# BLDC_Motor_Controller_2018_Rev1.net
KiCad netlist of a schematic drawn in EAGLE
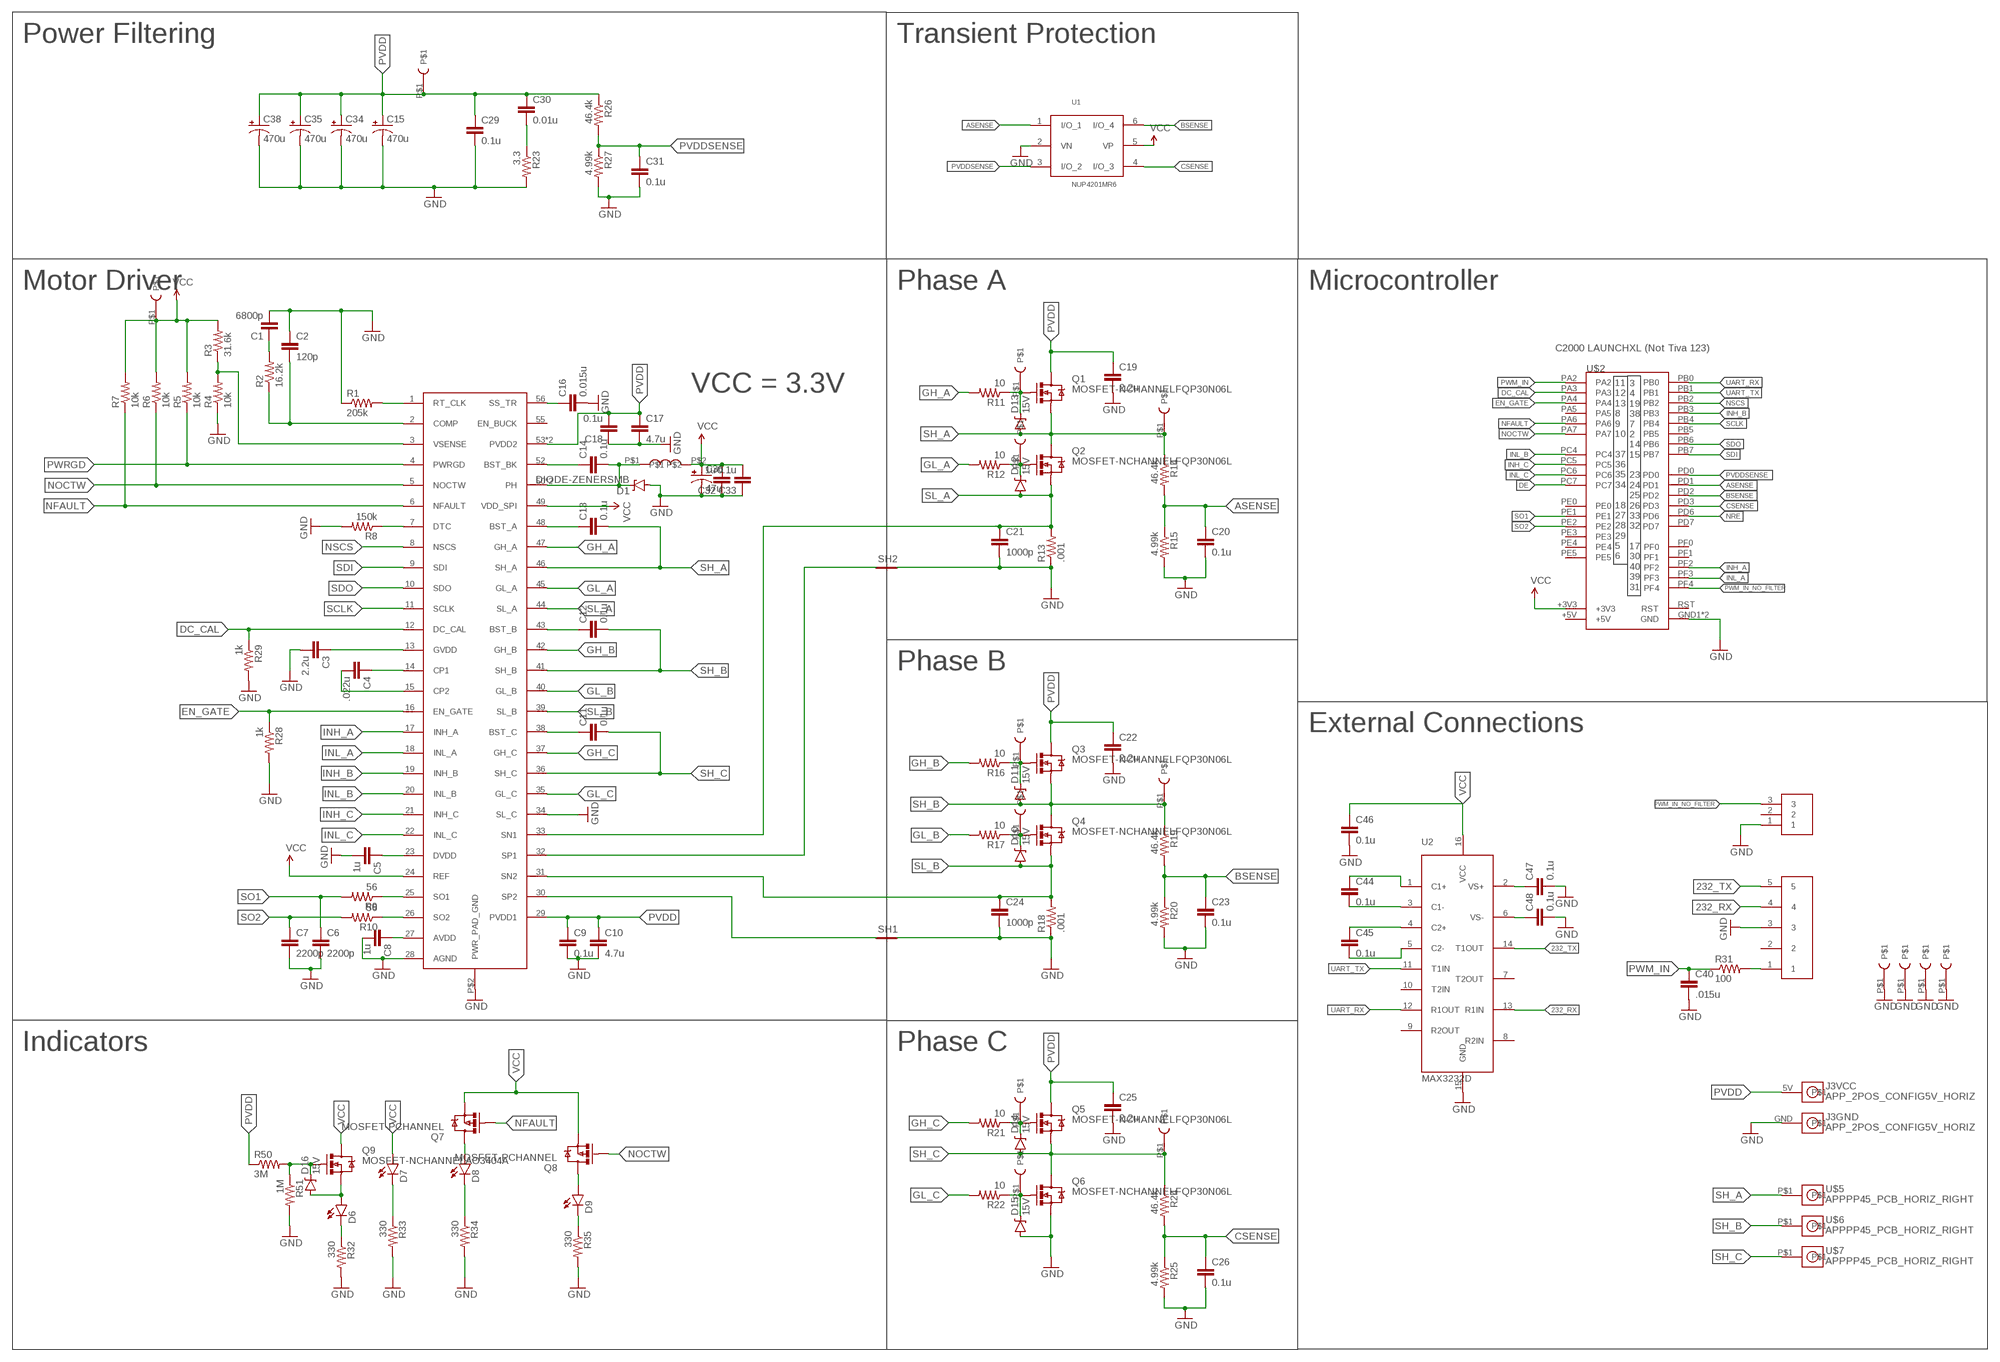
[diagram p0: schematic, sheet 1]

(export (version "E")
  (design (tool "Eeschema 10.0.6"))
  (components
    (comp (ref "C1")
      (value "6800p")
      (footprint "eagle-import:0805")
      (libsource (lib "eagle-import") (part "CAP0805"))
    )
    (comp (ref "C2")
      (value "120p")
      (footprint "eagle-import:0805")
      (libsource (lib "eagle-import") (part "CAP0805"))
    )
    (comp (ref "C3")
      (value "2.2u")
      (footprint "eagle-import:1206")
      (libsource (lib "eagle-import") (part "CAP1206"))
    )
    (comp (ref "C4")
      (value ".022u")
      (footprint "eagle-import:0805")
      (libsource (lib "eagle-import") (part "CAP0805"))
    )
    (comp (ref "C5")
      (value "1u")
      (footprint "eagle-import:0805")
      (libsource (lib "eagle-import") (part "CAP0805"))
    )
    (comp (ref "C6")
      (value "2200p")
      (footprint "eagle-import:0805")
      (libsource (lib "eagle-import") (part "CAP0805"))
    )
    (comp (ref "C7")
      (value "2200p")
      (footprint "eagle-import:0805")
      (libsource (lib "eagle-import") (part "CAP0805"))
    )
    (comp (ref "C8")
      (value "1u")
      (footprint "eagle-import:0805")
      (libsource (lib "eagle-import") (part "CAP0805"))
    )
    (comp (ref "C9")
      (value "0.1u")
      (footprint "eagle-import:0805")
      (libsource (lib "eagle-import") (part "CAP0805"))
    )
    (comp (ref "C10")
      (value "4.7u")
      (footprint "eagle-import:1206")
      (libsource (lib "eagle-import") (part "CAP1206"))
    )
    (comp (ref "C11")
      (value "0.1u")
      (footprint "eagle-import:0805")
      (libsource (lib "eagle-import") (part "CAP0805"))
    )
    (comp (ref "C12")
      (value "0.1u")
      (footprint "eagle-import:0805")
      (libsource (lib "eagle-import") (part "CAP0805"))
    )
    (comp (ref "C13")
      (value "0.1u")
      (footprint "eagle-import:0805")
      (libsource (lib "eagle-import") (part "CAP0805"))
    )
    (comp (ref "C14")
      (value "0.1u")
      (footprint "eagle-import:0805")
      (libsource (lib "eagle-import") (part "CAP0805"))
    )
    (comp (ref "C15")
      (value "470u")
      (footprint "eagle-import:CPOL-RADIAL-1000UF-25V")
      (libsource (lib "eagle-import") (part "CAP_POLPTH4"))
    )
    (comp (ref "C16")
      (value "0.015u")
      (footprint "eagle-import:0805")
      (libsource (lib "eagle-import") (part "CAP0805"))
    )
    (comp (ref "C17")
      (value "4.7u")
      (footprint "eagle-import:1206")
      (libsource (lib "eagle-import") (part "CAP1206"))
    )
    (comp (ref "C18")
      (value "0.1u")
      (footprint "eagle-import:0805")
      (libsource (lib "eagle-import") (part "CAP0805"))
    )
    (comp (ref "C19")
      (value "2.2u")
      (footprint "eagle-import:1206")
      (libsource (lib "eagle-import") (part "CAP1206"))
    )
    (comp (ref "C20")
      (value "0.1u")
      (footprint "eagle-import:0805")
      (libsource (lib "eagle-import") (part "CAP0805"))
    )
    (comp (ref "C21")
      (value "1000p")
      (footprint "eagle-import:0805")
      (libsource (lib "eagle-import") (part "CAP0805"))
    )
    (comp (ref "C22")
      (value "2.2u")
      (footprint "eagle-import:1206")
      (libsource (lib "eagle-import") (part "CAP1206"))
    )
    (comp (ref "C23")
      (value "0.1u")
      (footprint "eagle-import:0805")
      (libsource (lib "eagle-import") (part "CAP0805"))
    )
    (comp (ref "C24")
      (value "1000p")
      (footprint "eagle-import:0805")
      (libsource (lib "eagle-import") (part "CAP0805"))
    )
    (comp (ref "C25")
      (value "2.2u")
      (footprint "eagle-import:1206")
      (libsource (lib "eagle-import") (part "CAP1206"))
    )
    (comp (ref "C26")
      (value "0.1u")
      (footprint "eagle-import:0805")
      (libsource (lib "eagle-import") (part "CAP0805"))
    )
    (comp (ref "C29")
      (value "0.1u")
      (footprint "eagle-import:0805")
      (libsource (lib "eagle-import") (part "CAP0805"))
    )
    (comp (ref "C30")
      (value "0.01u")
      (footprint "eagle-import:0805")
      (libsource (lib "eagle-import") (part "CAP0805"))
    )
    (comp (ref "C31")
      (value "0.1u")
      (footprint "eagle-import:0805")
      (libsource (lib "eagle-import") (part "CAP0805"))
    )
    (comp (ref "C32")
      (value "1u")
      (footprint "eagle-import:0805")
      (libsource (lib "eagle-import") (part "CAP0805"))
    )
    (comp (ref "C33")
      (value "0.1u")
      (footprint "eagle-import:0805")
      (libsource (lib "eagle-import") (part "CAP0805"))
    )
    (comp (ref "C34")
      (value "470u")
      (footprint "eagle-import:CPOL-RADIAL-1000UF-25V")
      (libsource (lib "eagle-import") (part "CAP_POLPTH4"))
    )
    (comp (ref "C35")
      (value "470u")
      (footprint "eagle-import:CPOL-RADIAL-1000UF-25V")
      (libsource (lib "eagle-import") (part "CAP_POLPTH4"))
    )
    (comp (ref "C36")
      (value "47u")
      (footprint "eagle-import:CPOL-RADIAL-100UF-25V")
      (libsource (lib "eagle-import") (part "CAP_POLPTH1"))
    )
    (comp (ref "C38")
      (value "470u")
      (footprint "eagle-import:CPOL-RADIAL-1000UF-25V")
      (libsource (lib "eagle-import") (part "CAP_POLPTH4"))
    )
    (comp (ref "C40")
      (value ".015u")
      (footprint "eagle-import:0805")
      (libsource (lib "eagle-import") (part "CAP0805"))
    )
    (comp (ref "C44")
      (value "0.1u")
      (footprint "eagle-import:0805")
      (libsource (lib "eagle-import") (part "CAP0805"))
    )
    (comp (ref "C45")
      (value "0.1u")
      (footprint "eagle-import:0805")
      (libsource (lib "eagle-import") (part "CAP0805"))
    )
    (comp (ref "C46")
      (value "0.1u")
      (footprint "eagle-import:0805")
      (libsource (lib "eagle-import") (part "CAP0805"))
    )
    (comp (ref "C47")
      (value "0.1u")
      (footprint "eagle-import:0805")
      (libsource (lib "eagle-import") (part "CAP0805"))
    )
    (comp (ref "C48")
      (value "0.1u")
      (footprint "eagle-import:0805")
      (libsource (lib "eagle-import") (part "CAP0805"))
    )
    (comp (ref "D1")
      (value "DIODE-ZENERSMB")
      (footprint "eagle-import:SMB-DIODE")
      (libsource (lib "eagle-import") (part "DIODE-ZENERSMB"))
    )
    (comp (ref "D6")
      (value "LED1206")
      (footprint "eagle-import:LED-1206")
      (libsource (lib "eagle-import") (part "LED1206"))
    )
    (comp (ref "D7")
      (value "LED1206")
      (footprint "eagle-import:LED-1206")
      (libsource (lib "eagle-import") (part "LED1206"))
    )
    (comp (ref "D8")
      (value "LED1206")
      (footprint "eagle-import:LED-1206")
      (libsource (lib "eagle-import") (part "LED1206"))
    )
    (comp (ref "D9")
      (value "LED1206")
      (footprint "eagle-import:LED-1206")
      (libsource (lib "eagle-import") (part "LED1206"))
    )
    (comp (ref "D10")
      (value "15V")
      (footprint "eagle-import:SOD-323")
      (libsource (lib "eagle-import") (part "DIODE-ZENER3.3V"))
    )
    (comp (ref "D11")
      (value "15V")
      (footprint "eagle-import:SOD-323")
      (libsource (lib "eagle-import") (part "DIODE-ZENER3.3V"))
    )
    (comp (ref "D12")
      (value "15V")
      (footprint "eagle-import:SOD-323")
      (libsource (lib "eagle-import") (part "DIODE-ZENER3.3V"))
    )
    (comp (ref "D13")
      (value "15V")
      (footprint "eagle-import:SOD-323")
      (libsource (lib "eagle-import") (part "DIODE-ZENER3.3V"))
    )
    (comp (ref "D14")
      (value "15V")
      (footprint "eagle-import:SOD-323")
      (libsource (lib "eagle-import") (part "DIODE-ZENER3.3V"))
    )
    (comp (ref "D15")
      (value "15V")
      (footprint "eagle-import:SOD-323")
      (libsource (lib "eagle-import") (part "DIODE-ZENER3.3V"))
    )
    (comp (ref "D16")
      (value "15V")
      (footprint "eagle-import:SOD-323")
      (libsource (lib "eagle-import") (part "DIODE-ZENER3.3V"))
    )
    (comp (ref "J1")
      (value "SL03THROUGH_HOLE")
      (footprint "eagle-import:MOLEX_SL_03_TH")
      (fields (field (name "PARTNO") "0705550002"))
      (libsource (lib "eagle-import") (part "SL03THROUGH_HOLE"))
    )
    (comp (ref "J3")
      (value "APP_2POS_CONFIG5V_HORIZ")
      (footprint "eagle-import:APP45_5V_HORIZ_CONFIG")
      (libsource (lib "eagle-import") (part "APP_2POS_CONFIG5V_HORIZ"))
    )
    (comp (ref "Q1")
      (value "MOSFET-NCHANNELFQP30N06L")
      (footprint "eagle-import:TO220V")
      (libsource (lib "eagle-import") (part "MOSFET-NCHANNELFQP30N06L"))
    )
    (comp (ref "Q2")
      (value "MOSFET-NCHANNELFQP30N06L")
      (footprint "eagle-import:TO220V")
      (libsource (lib "eagle-import") (part "MOSFET-NCHANNELFQP30N06L"))
    )
    (comp (ref "Q3")
      (value "MOSFET-NCHANNELFQP30N06L")
      (footprint "eagle-import:TO220V")
      (libsource (lib "eagle-import") (part "MOSFET-NCHANNELFQP30N06L"))
    )
    (comp (ref "Q4")
      (value "MOSFET-NCHANNELFQP30N06L")
      (footprint "eagle-import:TO220V")
      (libsource (lib "eagle-import") (part "MOSFET-NCHANNELFQP30N06L"))
    )
    (comp (ref "Q5")
      (value "MOSFET-NCHANNELFQP30N06L")
      (footprint "eagle-import:TO220V")
      (libsource (lib "eagle-import") (part "MOSFET-NCHANNELFQP30N06L"))
    )
    (comp (ref "Q6")
      (value "MOSFET-NCHANNELFQP30N06L")
      (footprint "eagle-import:TO220V")
      (libsource (lib "eagle-import") (part "MOSFET-NCHANNELFQP30N06L"))
    )
    (comp (ref "Q7")
      (value "MOSFET-PCHANNEL")
      (footprint "eagle-import:SOT23-3")
      (libsource (lib "eagle-import") (part "MOSFET-PCHANNEL"))
    )
    (comp (ref "Q8")
      (value "MOSFET-PCHANNEL")
      (footprint "eagle-import:SOT23-3")
      (libsource (lib "eagle-import") (part "MOSFET-PCHANNEL"))
    )
    (comp (ref "Q9")
      (value "MOSFET-NCHANNELAO3404A")
      (footprint "eagle-import:SOT23-3")
      (libsource (lib "eagle-import") (part "MOSFET-NCHANNELAO3404A"))
    )
    (comp (ref "R1")
      (value "205k")
      (footprint "eagle-import:0805")
      (libsource (lib "eagle-import") (part "RESISTOR0805-RES"))
    )
    (comp (ref "R2")
      (value "16.2k")
      (footprint "eagle-import:0805")
      (libsource (lib "eagle-import") (part "RESISTOR0805-RES"))
    )
    (comp (ref "R3")
      (value "31.6k")
      (footprint "eagle-import:0805")
      (libsource (lib "eagle-import") (part "RESISTOR0805-RES"))
    )
    (comp (ref "R4")
      (value "10k")
      (footprint "eagle-import:0805")
      (libsource (lib "eagle-import") (part "RESISTOR0805-RES"))
    )
    (comp (ref "R5")
      (value "10k")
      (footprint "eagle-import:0805")
      (libsource (lib "eagle-import") (part "RESISTOR0805-RES"))
    )
    (comp (ref "R6")
      (value "10k")
      (footprint "eagle-import:0805")
      (libsource (lib "eagle-import") (part "RESISTOR0805-RES"))
    )
    (comp (ref "R7")
      (value "10k")
      (footprint "eagle-import:0805")
      (libsource (lib "eagle-import") (part "RESISTOR0805-RES"))
    )
    (comp (ref "R8")
      (value "150k")
      (footprint "eagle-import:0805")
      (libsource (lib "eagle-import") (part "RESISTOR0805-RES"))
    )
    (comp (ref "R9")
      (value "56")
      (footprint "eagle-import:0805")
      (libsource (lib "eagle-import") (part "RESISTOR0805-RES"))
    )
    (comp (ref "R10")
      (value "56")
      (footprint "eagle-import:0805")
      (libsource (lib "eagle-import") (part "RESISTOR0805-RES"))
    )
    (comp (ref "R11")
      (value "10")
      (footprint "eagle-import:0805")
      (libsource (lib "eagle-import") (part "RESISTOR0805-RES"))
    )
    (comp (ref "R12")
      (value "10")
      (footprint "eagle-import:0805")
      (libsource (lib "eagle-import") (part "RESISTOR0805-RES"))
    )
    (comp (ref "R13")
      (value ".001")
      (footprint "eagle-import:1206")
      (libsource (lib "eagle-import") (part "RESISTOR1206"))
    )
    (comp (ref "R14")
      (value "46.4k")
      (footprint "eagle-import:0805")
      (libsource (lib "eagle-import") (part "RESISTOR0805-RES"))
    )
    (comp (ref "R15")
      (value "4.99k")
      (footprint "eagle-import:0805")
      (libsource (lib "eagle-import") (part "RESISTOR0805-RES"))
    )
    (comp (ref "R16")
      (value "10")
      (footprint "eagle-import:0805")
      (libsource (lib "eagle-import") (part "RESISTOR0805-RES"))
    )
    (comp (ref "R17")
      (value "10")
      (footprint "eagle-import:0805")
      (libsource (lib "eagle-import") (part "RESISTOR0805-RES"))
    )
    (comp (ref "R18")
      (value ".001")
      (footprint "eagle-import:1206")
      (libsource (lib "eagle-import") (part "RESISTOR1206"))
    )
    (comp (ref "R19")
      (value "46.4k")
      (footprint "eagle-import:0805")
      (libsource (lib "eagle-import") (part "RESISTOR0805-RES"))
    )
    (comp (ref "R20")
      (value "4.99k")
      (footprint "eagle-import:0805")
      (libsource (lib "eagle-import") (part "RESISTOR0805-RES"))
    )
    (comp (ref "R21")
      (value "10")
      (footprint "eagle-import:0805")
      (libsource (lib "eagle-import") (part "RESISTOR0805-RES"))
    )
    (comp (ref "R22")
      (value "10")
      (footprint "eagle-import:0805")
      (libsource (lib "eagle-import") (part "RESISTOR0805-RES"))
    )
    (comp (ref "R23")
      (value "3.3")
      (footprint "eagle-import:0805")
      (libsource (lib "eagle-import") (part "RESISTOR0805-RES"))
    )
    (comp (ref "R24")
      (value "46.4k")
      (footprint "eagle-import:0805")
      (libsource (lib "eagle-import") (part "RESISTOR0805-RES"))
    )
    (comp (ref "R25")
      (value "4.99k")
      (footprint "eagle-import:0805")
      (libsource (lib "eagle-import") (part "RESISTOR0805-RES"))
    )
    (comp (ref "R26")
      (value "46.4k")
      (footprint "eagle-import:0805")
      (libsource (lib "eagle-import") (part "RESISTOR0805-RES"))
    )
    (comp (ref "R27")
      (value "4.99k")
      (footprint "eagle-import:0805")
      (libsource (lib "eagle-import") (part "RESISTOR0805-RES"))
    )
    (comp (ref "R28")
      (value "1k")
      (footprint "eagle-import:0805")
      (libsource (lib "eagle-import") (part "RESISTOR0805-RES"))
    )
    (comp (ref "R29")
      (value "1k")
      (footprint "eagle-import:0805")
      (libsource (lib "eagle-import") (part "RESISTOR0805-RES"))
    )
    (comp (ref "R31")
      (value "100")
      (footprint "eagle-import:0805")
      (libsource (lib "eagle-import") (part "RESISTOR0805-RES"))
    )
    (comp (ref "R32")
      (value "330")
      (footprint "eagle-import:0805")
      (libsource (lib "eagle-import") (part "RESISTOR0805-RES"))
    )
    (comp (ref "R33")
      (value "330")
      (footprint "eagle-import:0805")
      (libsource (lib "eagle-import") (part "RESISTOR0805-RES"))
    )
    (comp (ref "R34")
      (value "330")
      (footprint "eagle-import:0805")
      (libsource (lib "eagle-import") (part "RESISTOR0805-RES"))
    )
    (comp (ref "R35")
      (value "330")
      (footprint "eagle-import:0805")
      (libsource (lib "eagle-import") (part "RESISTOR0805-RES"))
    )
    (comp (ref "R50")
      (value "3M")
      (footprint "eagle-import:0805")
      (libsource (lib "eagle-import") (part "RESISTOR0805-RES"))
    )
    (comp (ref "R51")
      (value "1M")
      (footprint "eagle-import:0805")
      (libsource (lib "eagle-import") (part "RESISTOR0805-RES"))
    )
    (comp (ref "SH1")
      (value "SHORT-HT5")
      (footprint "eagle-import:SHORT_TOP-50")
      (libsource (lib "eagle-import") (part "SHORT-HT5"))
    )
    (comp (ref "SH2")
      (value "SHORT-HT5")
      (footprint "eagle-import:SHORT_TOP-50")
      (libsource (lib "eagle-import") (part "SHORT-HT5"))
    )
    (comp (ref "U$1")
      (value "DRV8301")
      (footprint "eagle-import:DCA")
      (libsource (lib "eagle-import") (part "DRV8301"))
    )
    (comp (ref "U$2")
      (value "TIVA-C")
      (footprint "eagle-import:TIVA-C")
      (libsource (lib "eagle-import") (part "TIVA-C"))
    )
    (comp (ref "U$4")
      (value "5PIN")
      (footprint "eagle-import:5PIN")
      (libsource (lib "eagle-import") (part "5PIN"))
    )
    (comp (ref "U$5")
      (value "APPPP45_PCB_HORIZ_RIGHT")
      (footprint "eagle-import:APP45_PCB_HORIZ_RIGHT")
      (libsource (lib "eagle-import") (part "APPPP45_PCB_HORIZ_RIGHT"))
    )
    (comp (ref "U$6")
      (value "APPPP45_PCB_HORIZ_RIGHT")
      (footprint "eagle-import:APP45_PCB_HORIZ_RIGHT")
      (libsource (lib "eagle-import") (part "APPPP45_PCB_HORIZ_RIGHT"))
    )
    (comp (ref "U$7")
      (value "APPPP45_PCB_HORIZ_RIGHT")
      (footprint "eagle-import:APP45_PCB_HORIZ_RIGHT")
      (libsource (lib "eagle-import") (part "APPPP45_PCB_HORIZ_RIGHT"))
    )
    (comp (ref "U$10")
      (value "TEST_POINT_0.1INDIAM")
      (footprint "eagle-import:TEST_POINT_0.1INDIAM")
      (libsource (lib "eagle-import") (part "TEST_POINT_0.1INDIAM"))
    )
    (comp (ref "U$11")
      (value "TEST_POINT_0.1INDIAM")
      (footprint "eagle-import:TEST_POINT_0.1INDIAM")
      (libsource (lib "eagle-import") (part "TEST_POINT_0.1INDIAM"))
    )
    (comp (ref "U$12")
      (value "TEST_POINT_0.1INDIAM")
      (footprint "eagle-import:TEST_POINT_0.1INDIAM")
      (libsource (lib "eagle-import") (part "TEST_POINT_0.1INDIAM"))
    )
    (comp (ref "U$14")
      (value "33u")
      (footprint "eagle-import:INDUCTOR_DR74")
      (libsource (lib "eagle-import") (part "INDUCTOR_DR74"))
    )
    (comp (ref "U$15")
      (value "TEST_POINT_0.1INDIAM")
      (footprint "eagle-import:TEST_POINT_0.1INDIAM")
      (libsource (lib "eagle-import") (part "TEST_POINT_0.1INDIAM"))
    )
    (comp (ref "U$16")
      (value "TEST_POINT_0.1INDIAM")
      (footprint "eagle-import:TEST_POINT_0.1INDIAM")
      (libsource (lib "eagle-import") (part "TEST_POINT_0.1INDIAM"))
    )
    (comp (ref "U$17")
      (value "TEST_POINT_0.1INDIAM")
      (footprint "eagle-import:TEST_POINT_0.1INDIAM")
      (libsource (lib "eagle-import") (part "TEST_POINT_0.1INDIAM"))
    )
    (comp (ref "U$18")
      (value "TEST_POINT_0.1INDIAM")
      (footprint "eagle-import:TEST_POINT_0.1INDIAM")
      (libsource (lib "eagle-import") (part "TEST_POINT_0.1INDIAM"))
    )
    (comp (ref "U$19")
      (value "TEST_POINT_0.1INDIAM")
      (footprint "eagle-import:TEST_POINT_0.1INDIAM")
      (libsource (lib "eagle-import") (part "TEST_POINT_0.1INDIAM"))
    )
    (comp (ref "U$20")
      (value "TEST_POINT_0.1INDIAM")
      (footprint "eagle-import:TEST_POINT_0.1INDIAM")
      (libsource (lib "eagle-import") (part "TEST_POINT_0.1INDIAM"))
    )
    (comp (ref "U$24")
      (value "TEST_POINT_0.1INDIAM")
      (footprint "eagle-import:TEST_POINT_0.1INDIAM")
      (libsource (lib "eagle-import") (part "TEST_POINT_0.1INDIAM"))
    )
    (comp (ref "U$25")
      (value "TEST_POINT_0.1INDIAM")
      (footprint "eagle-import:TEST_POINT_0.1INDIAM")
      (libsource (lib "eagle-import") (part "TEST_POINT_0.1INDIAM"))
    )
    (comp (ref "U$26")
      (value "TEST_POINT_0.1INDIAM")
      (footprint "eagle-import:TEST_POINT_0.1INDIAM")
      (libsource (lib "eagle-import") (part "TEST_POINT_0.1INDIAM"))
    )
    (comp (ref "U$27")
      (value "TEST_POINT_0.1INDIAM")
      (footprint "eagle-import:TEST_POINT_0.1INDIAM")
      (libsource (lib "eagle-import") (part "TEST_POINT_0.1INDIAM"))
    )
    (comp (ref "U$28")
      (value "TEST_POINT_0.1INDIAM")
      (footprint "eagle-import:TEST_POINT_0.1INDIAM")
      (libsource (lib "eagle-import") (part "TEST_POINT_0.1INDIAM"))
    )
    (comp (ref "U$29")
      (value "TEST_POINT_0.1INDIAM")
      (footprint "eagle-import:TEST_POINT_0.1INDIAM")
      (libsource (lib "eagle-import") (part "TEST_POINT_0.1INDIAM"))
    )
    (comp (ref "U1")
      (value "NUP4201MR6")
      (footprint "eagle-import:TSOP-6")
      (libsource (lib "eagle-import") (part "NUP4201MR6"))
    )
    (comp (ref "U2")
      (value "MAX3232D")
      (footprint "eagle-import:SOIC16")
      (libsource (lib "eagle-import") (part "MAX232D3"))
    )
  )
  (nets
    (net (code "1") (name "/+5V") (class "Default")
      (node (ref "U$2") (pin "+5V") (pinfunction "+5V_+5V") (pintype "power_in"))
    )
    (net (code "2") (name "/RST") (class "Default")
      (node (ref "U$2") (pin "RST") (pinfunction "RST_RST") (pintype "power_in"))
    )
    (net (code "3") (name "232_RX") (class "Default")
      (node (ref "U$4") (pin "4") (pinfunction "4_4") (pintype "bidirectional"))
      (node (ref "U2") (pin "13") (pinfunction "R1IN_13") (pintype "bidirectional"))
    )
    (net (code "4") (name "232_TX") (class "Default")
      (node (ref "U$4") (pin "5") (pinfunction "5_5") (pintype "bidirectional"))
      (node (ref "U2") (pin "14") (pinfunction "T1OUT_14") (pintype "bidirectional"))
    )
    (net (code "5") (name "ASENSE") (class "Default")
      (node (ref "C20") (pin "1") (pinfunction "1_1") (pintype "passive"))
      (node (ref "R14") (pin "2") (pinfunction "2_2") (pintype "passive"))
      (node (ref "R15") (pin "1") (pinfunction "1_1") (pintype "passive"))
      (node (ref "U$2") (pin "PD1") (pinfunction "PD1_PD1") (pintype "bidirectional"))
      (node (ref "U1") (pin "1") (pinfunction "I/O_1_1") (pintype "bidirectional"))
    )
    (net (code "6") (name "BSENSE") (class "Default")
      (node (ref "C23") (pin "1") (pinfunction "1_1") (pintype "passive"))
      (node (ref "R19") (pin "2") (pinfunction "2_2") (pintype "passive"))
      (node (ref "R20") (pin "1") (pinfunction "1_1") (pintype "passive"))
      (node (ref "U$2") (pin "PD2") (pinfunction "PD2_PD2") (pintype "bidirectional"))
      (node (ref "U1") (pin "6") (pinfunction "I/O_4_6") (pintype "bidirectional"))
    )
    (net (code "7") (name "CSENSE") (class "Default")
      (node (ref "C26") (pin "1") (pinfunction "1_1") (pintype "passive"))
      (node (ref "R24") (pin "2") (pinfunction "2_2") (pintype "passive"))
      (node (ref "R25") (pin "1") (pinfunction "1_1") (pintype "passive"))
      (node (ref "U$2") (pin "PD3") (pinfunction "PD3_PD3") (pintype "bidirectional"))
      (node (ref "U1") (pin "4") (pinfunction "I/O_3_4") (pintype "bidirectional"))
    )
    (net (code "8") (name "DC_CAL") (class "Default")
      (node (ref "R29") (pin "1") (pinfunction "1_1") (pintype "passive"))
      (node (ref "U$1") (pin "12") (pinfunction "DC_CAL_12") (pintype "bidirectional"))
      (node (ref "U$2") (pin "PA3") (pinfunction "PA3_PA3") (pintype "bidirectional"))
    )
    (net (code "9") (name "DE") (class "Default")
      (node (ref "U$2") (pin "PC7") (pinfunction "PC7_PC7") (pintype "bidirectional"))
    )
    (net (code "10") (name "EN_GATE") (class "Default")
      (node (ref "R28") (pin "1") (pinfunction "1_1") (pintype "passive"))
      (node (ref "U$1") (pin "16") (pinfunction "EN_GATE_16") (pintype "bidirectional"))
      (node (ref "U$2") (pin "PA4") (pinfunction "PA4_PA4") (pintype "bidirectional"))
    )
    (net (code "11") (name "GH_A") (class "Default")
      (node (ref "R11") (pin "2") (pinfunction "2_2") (pintype "passive"))
      (node (ref "U$1") (pin "47") (pinfunction "GH_A_47") (pintype "bidirectional"))
    )
    (net (code "12") (name "GH_B") (class "Default")
      (node (ref "R16") (pin "2") (pinfunction "2_2") (pintype "passive"))
      (node (ref "U$1") (pin "42") (pinfunction "GH_B_42") (pintype "bidirectional"))
    )
    (net (code "13") (name "GH_C") (class "Default")
      (node (ref "R21") (pin "2") (pinfunction "2_2") (pintype "passive"))
      (node (ref "U$1") (pin "37") (pinfunction "GH_C_37") (pintype "bidirectional"))
    )
    (net (code "14") (name "GL_A") (class "Default")
      (node (ref "R12") (pin "2") (pinfunction "2_2") (pintype "passive"))
      (node (ref "U$1") (pin "45") (pinfunction "GL_A_45") (pintype "bidirectional"))
    )
    (net (code "15") (name "GL_B") (class "Default")
      (node (ref "R17") (pin "2") (pinfunction "2_2") (pintype "passive"))
      (node (ref "U$1") (pin "40") (pinfunction "GL_B_40") (pintype "bidirectional"))
    )
    (net (code "16") (name "GL_C") (class "Default")
      (node (ref "R22") (pin "2") (pinfunction "2_2") (pintype "passive"))
      (node (ref "U$1") (pin "35") (pinfunction "GL_C_35") (pintype "bidirectional"))
    )
    (net (code "17") (name "GND") (class "Default")
      (node (ref "C1") (pin "2") (pinfunction "2_2") (pintype "passive"))
      (node (ref "C10") (pin "2") (pinfunction "2_2") (pintype "passive"))
      (node (ref "C15") (pin "2") (pinfunction "-_2") (pintype "passive"))
      (node (ref "C16") (pin "2") (pinfunction "2_2") (pintype "passive"))
      (node (ref "C17") (pin "2") (pinfunction "2_2") (pintype "passive"))
      (node (ref "C18") (pin "1") (pinfunction "1_1") (pintype "passive"))
      (node (ref "C19") (pin "2") (pinfunction "2_2") (pintype "passive"))
      (node (ref "C2") (pin "1") (pinfunction "1_1") (pintype "passive"))
      (node (ref "C20") (pin "2") (pinfunction "2_2") (pintype "passive"))
      (node (ref "C21") (pin "2") (pinfunction "2_2") (pintype "passive"))
      (node (ref "C22") (pin "2") (pinfunction "2_2") (pintype "passive"))
      (node (ref "C23") (pin "2") (pinfunction "2_2") (pintype "passive"))
      (node (ref "C24") (pin "2") (pinfunction "2_2") (pintype "passive"))
      (node (ref "C25") (pin "2") (pinfunction "2_2") (pintype "passive"))
      (node (ref "C26") (pin "2") (pinfunction "2_2") (pintype "passive"))
      (node (ref "C29") (pin "2") (pinfunction "2_2") (pintype "passive"))
      (node (ref "C3") (pin "2") (pinfunction "2_2") (pintype "passive"))
      (node (ref "C31") (pin "2") (pinfunction "2_2") (pintype "passive"))
      (node (ref "C32") (pin "1") (pinfunction "1_1") (pintype "passive"))
      (node (ref "C33") (pin "1") (pinfunction "1_1") (pintype "passive"))
      (node (ref "C34") (pin "2") (pinfunction "-_2") (pintype "passive"))
      (node (ref "C35") (pin "2") (pinfunction "-_2") (pintype "passive"))
      (node (ref "C36") (pin "2") (pinfunction "-_2") (pintype "passive"))
      (node (ref "C38") (pin "2") (pinfunction "-_2") (pintype "passive"))
      (node (ref "C40") (pin "2") (pinfunction "2_2") (pintype "passive"))
      (node (ref "C46") (pin "2") (pinfunction "2_2") (pintype "passive"))
      (node (ref "C47") (pin "2") (pinfunction "2_2") (pintype "passive"))
      (node (ref "C48") (pin "2") (pinfunction "2_2") (pintype "passive"))
      (node (ref "C5") (pin "2") (pinfunction "2_2") (pintype "passive"))
      (node (ref "C6") (pin "2") (pinfunction "2_2") (pintype "passive"))
      (node (ref "C7") (pin "2") (pinfunction "2_2") (pintype "passive"))
      (node (ref "C8") (pin "2") (pinfunction "2_2") (pintype "passive"))
      (node (ref "C9") (pin "2") (pinfunction "2_2") (pintype "passive"))
      (node (ref "D1") (pin "A") (pinfunction "A_A") (pintype "passive"))
      (node (ref "D15") (pin "A") (pinfunction "A_A") (pintype "passive"))
      (node (ref "J1") (pin "1") (pinfunction "1_1") (pintype "bidirectional"))
      (node (ref "J3") (pin "GND") (pinfunction "P$1_GND") (pintype "bidirectional"))
      (node (ref "Q6") (pin "3") (pinfunction "S_3") (pintype "passive"))
      (node (ref "R1") (pin "1") (pinfunction "1_1") (pintype "passive"))
      (node (ref "R13") (pin "1") (pinfunction "1_1") (pintype "passive"))
      (node (ref "R15") (pin "2") (pinfunction "2_2") (pintype "passive"))
      (node (ref "R18") (pin "1") (pinfunction "1_1") (pintype "passive"))
      (node (ref "R20") (pin "2") (pinfunction "2_2") (pintype "passive"))
      (node (ref "R23") (pin "2") (pinfunction "2_2") (pintype "passive"))
      (node (ref "R25") (pin "2") (pinfunction "2_2") (pintype "passive"))
      (node (ref "R27") (pin "2") (pinfunction "2_2") (pintype "passive"))
      (node (ref "R28") (pin "2") (pinfunction "2_2") (pintype "passive"))
      (node (ref "R29") (pin "2") (pinfunction "2_2") (pintype "passive"))
      (node (ref "R32") (pin "2") (pinfunction "2_2") (pintype "passive"))
      (node (ref "R33") (pin "2") (pinfunction "2_2") (pintype "passive"))
      (node (ref "R34") (pin "2") (pinfunction "2_2") (pintype "passive"))
      (node (ref "R35") (pin "2") (pinfunction "2_2") (pintype "passive"))
      (node (ref "R4") (pin "1") (pinfunction "1_1") (pintype "passive"))
      (node (ref "R51") (pin "2") (pinfunction "2_2") (pintype "passive"))
      (node (ref "R8") (pin "2") (pinfunction "2_2") (pintype "passive"))
      (node (ref "SH1") (pin "2") (pinfunction "P$2_2") (pintype "bidirectional"))
      (node (ref "SH2") (pin "2") (pinfunction "P$2_2") (pintype "bidirectional"))
      (node (ref "U$1") (pin "28") (pinfunction "AGND_28") (pintype "bidirectional"))
      (node (ref "U$1") (pin "34") (pinfunction "SL_C_34") (pintype "bidirectional"))
      (node (ref "U$1") (pin "P$2") (pinfunction "PWR_PAD_GND_P$2") (pintype "bidirectional"))
      (node (ref "U$2") (pin "GND1") (pinfunction "GND_GND1") (pintype "power_in"))
      (node (ref "U$2") (pin "GND2") (pinfunction "GND_GND2") (pintype "power_in"))
      (node (ref "U$26") (pin "P$1") (pinfunction "P$1_P$1") (pintype "bidirectional"))
      (node (ref "U$27") (pin "P$1") (pinfunction "P$1_P$1") (pintype "bidirectional"))
      (node (ref "U$28") (pin "P$1") (pinfunction "P$1_P$1") (pintype "bidirectional"))
      (node (ref "U$29") (pin "P$1") (pinfunction "P$1_P$1") (pintype "bidirectional"))
      (node (ref "U$4") (pin "3") (pinfunction "3_3") (pintype "bidirectional"))
      (node (ref "U1") (pin "2") (pinfunction "VN_2") (pintype "bidirectional"))
      (node (ref "U2") (pin "15") (pinfunction "GND_15") (pintype "bidirectional"))
    )
    (net (code "18") (name "INH_A") (class "Default")
      (node (ref "U$1") (pin "17") (pinfunction "INH_A_17") (pintype "bidirectional"))
      (node (ref "U$2") (pin "PF2") (pinfunction "PF2_PF2") (pintype "bidirectional"))
    )
    (net (code "19") (name "INH_B") (class "Default")
      (node (ref "U$1") (pin "19") (pinfunction "INH_B_19") (pintype "bidirectional"))
      (node (ref "U$2") (pin "PB3") (pinfunction "PB3_PB3") (pintype "bidirectional"))
    )
    (net (code "20") (name "INH_C") (class "Default")
      (node (ref "U$1") (pin "21") (pinfunction "INH_C_21") (pintype "bidirectional"))
      (node (ref "U$2") (pin "PC5") (pinfunction "PC5_PC5") (pintype "bidirectional"))
    )
    (net (code "21") (name "INL_A") (class "Default")
      (node (ref "U$1") (pin "18") (pinfunction "INL_A_18") (pintype "bidirectional"))
      (node (ref "U$2") (pin "PF3") (pinfunction "PF3_PF3") (pintype "bidirectional"))
    )
    (net (code "22") (name "INL_B") (class "Default")
      (node (ref "U$1") (pin "20") (pinfunction "INL_B_20") (pintype "bidirectional"))
      (node (ref "U$2") (pin "PC4") (pinfunction "PC4_PC4") (pintype "bidirectional"))
    )
    (net (code "23") (name "INL_C") (class "Default")
      (node (ref "U$1") (pin "22") (pinfunction "INL_C_22") (pintype "bidirectional"))
      (node (ref "U$2") (pin "PC6") (pinfunction "PC6_PC6") (pintype "bidirectional"))
    )
    (net (code "24") (name "NFAULT") (class "Default")
      (node (ref "Q7") (pin "1") (pinfunction "G_1") (pintype "passive"))
      (node (ref "R7") (pin "1") (pinfunction "1_1") (pintype "passive"))
      (node (ref "U$1") (pin "6") (pinfunction "NFAULT_6") (pintype "bidirectional"))
      (node (ref "U$2") (pin "PA6") (pinfunction "PA6_PA6") (pintype "bidirectional"))
    )
    (net (code "25") (name "NOCTW") (class "Default")
      (node (ref "Q8") (pin "1") (pinfunction "G_1") (pintype "passive"))
      (node (ref "R6") (pin "1") (pinfunction "1_1") (pintype "passive"))
      (node (ref "U$1") (pin "5") (pinfunction "NOCTW_5") (pintype "bidirectional"))
      (node (ref "U$2") (pin "PA7") (pinfunction "PA7_PA7") (pintype "bidirectional"))
    )
    (net (code "26") (name "NRE") (class "Default")
      (node (ref "U$2") (pin "PD6") (pinfunction "PD6_PD6") (pintype "bidirectional"))
    )
    (net (code "27") (name "NSCS") (class "Default")
      (node (ref "U$1") (pin "8") (pinfunction "NSCS_8") (pintype "bidirectional"))
      (node (ref "U$2") (pin "PB2") (pinfunction "PB2_PB2") (pintype "bidirectional"))
    )
    (net (code "28") (name "Net-(C1-Pad1)") (class "Default")
      (node (ref "C1") (pin "1") (pinfunction "1_1") (pintype "passive"))
      (node (ref "R2") (pin "2") (pinfunction "2_2") (pintype "passive"))
    )
    (net (code "29") (name "Net-(C14-Pad2)") (class "Default")
      (node (ref "C14") (pin "2") (pinfunction "2_2") (pintype "passive"))
      (node (ref "D1") (pin "C") (pinfunction "C_C") (pintype "passive"))
      (node (ref "U$1") (pin "50") (pinfunction "PH_50") (pintype "bidirectional"))
      (node (ref "U$1") (pin "51") (pinfunction "PH_51") (pintype "bidirectional"))
      (node (ref "U$14") (pin "P$1") (pinfunction "P$1_P$1") (pintype "bidirectional"))
    )
    (net (code "30") (name "Net-(C30-Pad2)") (class "Default")
      (node (ref "C30") (pin "2") (pinfunction "2_2") (pintype "passive"))
      (node (ref "R23") (pin "1") (pinfunction "1_1") (pintype "passive"))
    )
    (net (code "31") (name "Net-(D6-PadC)") (class "Default")
      (node (ref "D6") (pin "C") (pinfunction "C_C") (pintype "passive"))
      (node (ref "R32") (pin "1") (pinfunction "1_1") (pintype "passive"))
    )
    (net (code "32") (name "Net-(D7-PadC)") (class "Default")
      (node (ref "D7") (pin "C") (pinfunction "C_C") (pintype "passive"))
      (node (ref "R33") (pin "1") (pinfunction "1_1") (pintype "passive"))
    )
    (net (code "33") (name "Net-(D8-PadC)") (class "Default")
      (node (ref "D8") (pin "C") (pinfunction "C_C") (pintype "passive"))
      (node (ref "R34") (pin "1") (pinfunction "1_1") (pintype "passive"))
    )
    (net (code "34") (name "Net-(D9-PadC)") (class "Default")
      (node (ref "D9") (pin "C") (pinfunction "C_C") (pintype "passive"))
      (node (ref "R35") (pin "1") (pinfunction "1_1") (pintype "passive"))
    )
    (net (code "35") (name "Net-(Q1-G)") (class "Default")
      (node (ref "D13") (pin "C") (pinfunction "C_C") (pintype "passive"))
      (node (ref "Q1") (pin "1") (pinfunction "G_1") (pintype "passive"))
      (node (ref "R11") (pin "1") (pinfunction "1_1") (pintype "passive"))
      (node (ref "U$12") (pin "P$1") (pinfunction "P$1_P$1") (pintype "bidirectional"))
    )
    (net (code "36") (name "Net-(Q2-G)") (class "Default")
      (node (ref "D12") (pin "C") (pinfunction "C_C") (pintype "passive"))
      (node (ref "Q2") (pin "1") (pinfunction "G_1") (pintype "passive"))
      (node (ref "R12") (pin "1") (pinfunction "1_1") (pintype "passive"))
      (node (ref "U$15") (pin "P$1") (pinfunction "P$1_P$1") (pintype "bidirectional"))
    )
    (net (code "37") (name "Net-(Q3-G)") (class "Default")
      (node (ref "D11") (pin "C") (pinfunction "C_C") (pintype "passive"))
      (node (ref "Q3") (pin "1") (pinfunction "G_1") (pintype "passive"))
      (node (ref "R16") (pin "1") (pinfunction "1_1") (pintype "passive"))
      (node (ref "U$16") (pin "P$1") (pinfunction "P$1_P$1") (pintype "bidirectional"))
    )
    (net (code "38") (name "Net-(Q4-G)") (class "Default")
      (node (ref "D10") (pin "C") (pinfunction "C_C") (pintype "passive"))
      (node (ref "Q4") (pin "1") (pinfunction "G_1") (pintype "passive"))
      (node (ref "R17") (pin "1") (pinfunction "1_1") (pintype "passive"))
      (node (ref "U$17") (pin "P$1") (pinfunction "P$1_P$1") (pintype "bidirectional"))
    )
    (net (code "39") (name "Net-(Q5-G)") (class "Default")
      (node (ref "D14") (pin "C") (pinfunction "C_C") (pintype "passive"))
      (node (ref "Q5") (pin "1") (pinfunction "G_1") (pintype "passive"))
      (node (ref "R21") (pin "1") (pinfunction "1_1") (pintype "passive"))
      (node (ref "U$18") (pin "P$1") (pinfunction "P$1_P$1") (pintype "bidirectional"))
    )
    (net (code "40") (name "Net-(Q6-G)") (class "Default")
      (node (ref "D15") (pin "C") (pinfunction "C_C") (pintype "passive"))
      (node (ref "Q6") (pin "1") (pinfunction "G_1") (pintype "passive"))
      (node (ref "R22") (pin "1") (pinfunction "1_1") (pintype "passive"))
      (node (ref "U$19") (pin "P$1") (pinfunction "P$1_P$1") (pintype "bidirectional"))
    )
    (net (code "41") (name "Net-(Q7-D)") (class "Default")
      (node (ref "D8") (pin "A") (pinfunction "A_A") (pintype "passive"))
      (node (ref "Q7") (pin "3") (pinfunction "D_3") (pintype "passive"))
    )
    (net (code "42") (name "Net-(Q8-D)") (class "Default")
      (node (ref "D9") (pin "A") (pinfunction "A_A") (pintype "passive"))
      (node (ref "Q8") (pin "3") (pinfunction "D_3") (pintype "passive"))
    )
    (net (code "43") (name "Net-(Q9-G)") (class "Default")
      (node (ref "D16") (pin "C") (pinfunction "C_C") (pintype "passive"))
      (node (ref "Q9") (pin "1") (pinfunction "G_1") (pintype "passive"))
      (node (ref "R50") (pin "2") (pinfunction "2_2") (pintype "passive"))
      (node (ref "R51") (pin "1") (pinfunction "1_1") (pintype "passive"))
    )
    (net (code "44") (name "Net-(Q9-S)") (class "Default")
      (node (ref "D16") (pin "A") (pinfunction "A_A") (pintype "passive"))
      (node (ref "D6") (pin "A") (pinfunction "A_A") (pintype "passive"))
      (node (ref "Q9") (pin "2") (pinfunction "S_2") (pintype "passive"))
    )
    (net (code "45") (name "Net-(R31-Pad2)") (class "Default")
      (node (ref "R31") (pin "2") (pinfunction "2_2") (pintype "passive"))
      (node (ref "U$4") (pin "1") (pinfunction "1_1") (pintype "bidirectional"))
    )
    (net (code "46") (name "Net-(SH1-P$1)") (class "Default")
      (node (ref "SH1") (pin "1") (pinfunction "P$1_1") (pintype "bidirectional"))
      (node (ref "U$1") (pin "30") (pinfunction "SP2_30") (pintype "bidirectional"))
    )
    (net (code "47") (name "Net-(SH2-P$1)") (class "Default")
      (node (ref "SH2") (pin "1") (pinfunction "P$1_1") (pintype "bidirectional"))
      (node (ref "U$1") (pin "32") (pinfunction "SP1_32") (pintype "bidirectional"))
    )
    (net (code "48") (name "Net-(U$1-AVDD)") (class "Default")
      (node (ref "C8") (pin "1") (pinfunction "1_1") (pintype "passive"))
      (node (ref "U$1") (pin "27") (pinfunction "AVDD_27") (pintype "bidirectional"))
    )
    (net (code "49") (name "Net-(U$1-BST_A)") (class "Default")
      (node (ref "C13") (pin "1") (pinfunction "1_1") (pintype "passive"))
      (node (ref "U$1") (pin "48") (pinfunction "BST_A_48") (pintype "bidirectional"))
    )
    (net (code "50") (name "Net-(U$1-BST_B)") (class "Default")
      (node (ref "C12") (pin "1") (pinfunction "1_1") (pintype "passive"))
      (node (ref "U$1") (pin "43") (pinfunction "BST_B_43") (pintype "bidirectional"))
    )
    (net (code "51") (name "Net-(U$1-BST_BK)") (class "Default")
      (node (ref "C14") (pin "1") (pinfunction "1_1") (pintype "passive"))
      (node (ref "U$1") (pin "52") (pinfunction "BST_BK_52") (pintype "bidirectional"))
    )
    (net (code "52") (name "Net-(U$1-BST_C)") (class "Default")
      (node (ref "C11") (pin "1") (pinfunction "1_1") (pintype "passive"))
      (node (ref "U$1") (pin "38") (pinfunction "BST_C_38") (pintype "bidirectional"))
    )
    (net (code "53") (name "Net-(U$1-COMP)") (class "Default")
      (node (ref "C2") (pin "2") (pinfunction "2_2") (pintype "passive"))
      (node (ref "R2") (pin "1") (pinfunction "1_1") (pintype "passive"))
      (node (ref "U$1") (pin "2") (pinfunction "COMP_2") (pintype "bidirectional"))
    )
    (net (code "54") (name "Net-(U$1-CP1)") (class "Default")
      (node (ref "C4") (pin "1") (pinfunction "1_1") (pintype "passive"))
      (node (ref "U$1") (pin "14") (pinfunction "CP1_14") (pintype "bidirectional"))
    )
    (net (code "55") (name "Net-(U$1-CP2)") (class "Default")
      (node (ref "C4") (pin "2") (pinfunction "2_2") (pintype "passive"))
      (node (ref "U$1") (pin "15") (pinfunction "CP2_15") (pintype "bidirectional"))
    )
    (net (code "56") (name "Net-(U$1-DTC)") (class "Default")
      (node (ref "R8") (pin "1") (pinfunction "1_1") (pintype "passive"))
      (node (ref "U$1") (pin "7") (pinfunction "DTC_7") (pintype "bidirectional"))
    )
    (net (code "57") (name "Net-(U$1-DVDD)") (class "Default")
      (node (ref "C5") (pin "1") (pinfunction "1_1") (pintype "passive"))
      (node (ref "U$1") (pin "23") (pinfunction "DVDD_23") (pintype "bidirectional"))
    )
    (net (code "58") (name "Net-(U$1-GVDD)") (class "Default")
      (node (ref "C3") (pin "1") (pinfunction "1_1") (pintype "passive"))
      (node (ref "U$1") (pin "13") (pinfunction "GVDD_13") (pintype "bidirectional"))
    )
    (net (code "59") (name "Net-(U$1-RT_CLK)") (class "Default")
      (node (ref "R1") (pin "2") (pinfunction "2_2") (pintype "passive"))
      (node (ref "U$1") (pin "1") (pinfunction "RT_CLK_1") (pintype "bidirectional"))
    )
    (net (code "60") (name "Net-(U$1-SO1)") (class "Default")
      (node (ref "R9") (pin "1") (pinfunction "1_1") (pintype "passive"))
      (node (ref "U$1") (pin "25") (pinfunction "SO1_25") (pintype "bidirectional"))
    )
    (net (code "61") (name "Net-(U$1-SO2)") (class "Default")
      (node (ref "R10") (pin "1") (pinfunction "1_1") (pintype "passive"))
      (node (ref "U$1") (pin "26") (pinfunction "SO2_26") (pintype "bidirectional"))
    )
    (net (code "62") (name "Net-(U$1-SS_TR)") (class "Default")
      (node (ref "C16") (pin "1") (pinfunction "1_1") (pintype "passive"))
      (node (ref "U$1") (pin "56") (pinfunction "SS_TR_56") (pintype "bidirectional"))
    )
    (net (code "63") (name "Net-(U$1-VSENSE)") (class "Default")
      (node (ref "R3") (pin "1") (pinfunction "1_1") (pintype "passive"))
      (node (ref "R4") (pin "2") (pinfunction "2_2") (pintype "passive"))
      (node (ref "U$1") (pin "3") (pinfunction "VSENSE_3") (pintype "bidirectional"))
    )
    (net (code "64") (name "Net-(U2-C1+)") (class "Default")
      (node (ref "C44") (pin "1") (pinfunction "1_1") (pintype "passive"))
      (node (ref "U2") (pin "1") (pinfunction "C1+_1") (pintype "bidirectional"))
    )
    (net (code "65") (name "Net-(U2-C1-)") (class "Default")
      (node (ref "C44") (pin "2") (pinfunction "2_2") (pintype "passive"))
      (node (ref "U2") (pin "3") (pinfunction "C1-_3") (pintype "bidirectional"))
    )
    (net (code "66") (name "Net-(U2-C2+)") (class "Default")
      (node (ref "C45") (pin "1") (pinfunction "1_1") (pintype "passive"))
      (node (ref "U2") (pin "4") (pinfunction "C2+_4") (pintype "bidirectional"))
    )
    (net (code "67") (name "Net-(U2-C2-)") (class "Default")
      (node (ref "C45") (pin "2") (pinfunction "2_2") (pintype "passive"))
      (node (ref "U2") (pin "5") (pinfunction "C2-_5") (pintype "bidirectional"))
    )
    (net (code "68") (name "Net-(U2-VS+)") (class "Default")
      (node (ref "C47") (pin "1") (pinfunction "1_1") (pintype "passive"))
      (node (ref "U2") (pin "2") (pinfunction "VS+_2") (pintype "bidirectional"))
    )
    (net (code "69") (name "Net-(U2-VS-)") (class "Default")
      (node (ref "C48") (pin "1") (pinfunction "1_1") (pintype "passive"))
      (node (ref "U2") (pin "6") (pinfunction "VS-_6") (pintype "bidirectional"))
    )
    (net (code "70") (name "PVDD") (class "Default")
      (node (ref "C10") (pin "1") (pinfunction "1_1") (pintype "passive"))
      (node (ref "C15") (pin "1") (pinfunction "+_1") (pintype "passive"))
      (node (ref "C17") (pin "1") (pinfunction "1_1") (pintype "passive"))
      (node (ref "C18") (pin "2") (pinfunction "2_2") (pintype "passive"))
      (node (ref "C19") (pin "1") (pinfunction "1_1") (pintype "passive"))
      (node (ref "C22") (pin "1") (pinfunction "1_1") (pintype "passive"))
      (node (ref "C25") (pin "1") (pinfunction "1_1") (pintype "passive"))
      (node (ref "C29") (pin "1") (pinfunction "1_1") (pintype "passive"))
      (node (ref "C30") (pin "1") (pinfunction "1_1") (pintype "passive"))
      (node (ref "C34") (pin "1") (pinfunction "+_1") (pintype "passive"))
      (node (ref "C35") (pin "1") (pinfunction "+_1") (pintype "passive"))
      (node (ref "C38") (pin "1") (pinfunction "+_1") (pintype "passive"))
      (node (ref "C9") (pin "1") (pinfunction "1_1") (pintype "passive"))
      (node (ref "J3") (pin "5V") (pinfunction "P$1_5V") (pintype "bidirectional"))
      (node (ref "Q1") (pin "2") (pinfunction "D_2") (pintype "passive"))
      (node (ref "Q3") (pin "2") (pinfunction "D_2") (pintype "passive"))
      (node (ref "Q5") (pin "2") (pinfunction "D_2") (pintype "passive"))
      (node (ref "R26") (pin "1") (pinfunction "1_1") (pintype "passive"))
      (node (ref "R50") (pin "1") (pinfunction "1_1") (pintype "passive"))
      (node (ref "U$1") (pin "29") (pinfunction "PVDD1_29") (pintype "bidirectional"))
      (node (ref "U$1") (pin "53") (pinfunction "PVDD2_53") (pintype "bidirectional"))
      (node (ref "U$1") (pin "54") (pinfunction "PVDD2_54") (pintype "bidirectional"))
      (node (ref "U$11") (pin "P$1") (pinfunction "P$1_P$1") (pintype "bidirectional"))
    )
    (net (code "71") (name "PVDDSENSE") (class "Default")
      (node (ref "C31") (pin "1") (pinfunction "1_1") (pintype "passive"))
      (node (ref "R26") (pin "2") (pinfunction "2_2") (pintype "passive"))
      (node (ref "R27") (pin "1") (pinfunction "1_1") (pintype "passive"))
      (node (ref "U$2") (pin "PD0") (pinfunction "PD0_PD0") (pintype "bidirectional"))
      (node (ref "U1") (pin "3") (pinfunction "I/O_2_3") (pintype "bidirectional"))
    )
    (net (code "72") (name "PWM_IN") (class "Default")
      (node (ref "C40") (pin "1") (pinfunction "1_1") (pintype "passive"))
      (node (ref "R31") (pin "1") (pinfunction "1_1") (pintype "passive"))
      (node (ref "U$2") (pin "PA2") (pinfunction "PA2_PA2") (pintype "bidirectional"))
    )
    (net (code "73") (name "PWM_IN_NO_FILTER") (class "Default")
      (node (ref "J1") (pin "3") (pinfunction "3_3") (pintype "bidirectional"))
      (node (ref "U$2") (pin "PF4") (pinfunction "PF4_PF4") (pintype "bidirectional"))
    )
    (net (code "74") (name "PWRGD") (class "Default")
      (node (ref "R5") (pin "1") (pinfunction "1_1") (pintype "passive"))
      (node (ref "U$1") (pin "4") (pinfunction "PWRGD_4") (pintype "bidirectional"))
    )
    (net (code "75") (name "SCLK") (class "Default")
      (node (ref "U$1") (pin "11") (pinfunction "SCLK_11") (pintype "bidirectional"))
      (node (ref "U$2") (pin "PB4") (pinfunction "PB4_PB4") (pintype "bidirectional"))
    )
    (net (code "76") (name "SDI") (class "Default")
      (node (ref "U$1") (pin "9") (pinfunction "SDI_9") (pintype "bidirectional"))
      (node (ref "U$2") (pin "PB7") (pinfunction "PB7_PB7") (pintype "bidirectional"))
    )
    (net (code "77") (name "SDO") (class "Default")
      (node (ref "U$1") (pin "10") (pinfunction "SDO_10") (pintype "bidirectional"))
      (node (ref "U$2") (pin "PB6") (pinfunction "PB6_PB6") (pintype "bidirectional"))
    )
    (net (code "78") (name "SH_A") (class "Default")
      (node (ref "C13") (pin "2") (pinfunction "2_2") (pintype "passive"))
      (node (ref "D13") (pin "A") (pinfunction "A_A") (pintype "passive"))
      (node (ref "Q1") (pin "3") (pinfunction "S_3") (pintype "passive"))
      (node (ref "Q2") (pin "2") (pinfunction "D_2") (pintype "passive"))
      (node (ref "R14") (pin "1") (pinfunction "1_1") (pintype "passive"))
      (node (ref "U$1") (pin "46") (pinfunction "SH_A_46") (pintype "bidirectional"))
      (node (ref "U$25") (pin "P$1") (pinfunction "P$1_P$1") (pintype "bidirectional"))
      (node (ref "U$5") (pin "P$1") (pinfunction "P$1_P$1") (pintype "bidirectional"))
    )
    (net (code "79") (name "SH_B") (class "Default")
      (node (ref "C12") (pin "2") (pinfunction "2_2") (pintype "passive"))
      (node (ref "D11") (pin "A") (pinfunction "A_A") (pintype "passive"))
      (node (ref "Q3") (pin "3") (pinfunction "S_3") (pintype "passive"))
      (node (ref "Q4") (pin "2") (pinfunction "D_2") (pintype "passive"))
      (node (ref "R19") (pin "1") (pinfunction "1_1") (pintype "passive"))
      (node (ref "U$1") (pin "41") (pinfunction "SH_B_41") (pintype "bidirectional"))
      (node (ref "U$24") (pin "P$1") (pinfunction "P$1_P$1") (pintype "bidirectional"))
      (node (ref "U$6") (pin "P$1") (pinfunction "P$1_P$1") (pintype "bidirectional"))
    )
    (net (code "80") (name "SH_C") (class "Default")
      (node (ref "C11") (pin "2") (pinfunction "2_2") (pintype "passive"))
      (node (ref "D14") (pin "A") (pinfunction "A_A") (pintype "passive"))
      (node (ref "Q5") (pin "3") (pinfunction "S_3") (pintype "passive"))
      (node (ref "Q6") (pin "2") (pinfunction "D_2") (pintype "passive"))
      (node (ref "R24") (pin "1") (pinfunction "1_1") (pintype "passive"))
      (node (ref "U$1") (pin "36") (pinfunction "SH_C_36") (pintype "bidirectional"))
      (node (ref "U$20") (pin "P$1") (pinfunction "P$1_P$1") (pintype "bidirectional"))
      (node (ref "U$7") (pin "P$1") (pinfunction "P$1_P$1") (pintype "bidirectional"))
    )
    (net (code "81") (name "SL_A") (class "Default")
      (node (ref "C21") (pin "1") (pinfunction "1_1") (pintype "passive"))
      (node (ref "D12") (pin "A") (pinfunction "A_A") (pintype "passive"))
      (node (ref "Q2") (pin "3") (pinfunction "S_3") (pintype "passive"))
      (node (ref "R13") (pin "2") (pinfunction "2_2") (pintype "passive"))
      (node (ref "U$1") (pin "33") (pinfunction "SN1_33") (pintype "bidirectional"))
      (node (ref "U$1") (pin "44") (pinfunction "SL_A_44") (pintype "bidirectional"))
    )
    (net (code "82") (name "SL_B") (class "Default")
      (node (ref "C24") (pin "1") (pinfunction "1_1") (pintype "passive"))
      (node (ref "D10") (pin "A") (pinfunction "A_A") (pintype "passive"))
      (node (ref "Q4") (pin "3") (pinfunction "S_3") (pintype "passive"))
      (node (ref "R18") (pin "2") (pinfunction "2_2") (pintype "passive"))
      (node (ref "U$1") (pin "31") (pinfunction "SN2_31") (pintype "bidirectional"))
      (node (ref "U$1") (pin "39") (pinfunction "SL_B_39") (pintype "bidirectional"))
    )
    (net (code "83") (name "SO1") (class "Default")
      (node (ref "C6") (pin "1") (pinfunction "1_1") (pintype "passive"))
      (node (ref "R9") (pin "2") (pinfunction "2_2") (pintype "passive"))
      (node (ref "U$2") (pin "PE1") (pinfunction "PE1_PE1") (pintype "bidirectional"))
    )
    (net (code "84") (name "SO2") (class "Default")
      (node (ref "C7") (pin "1") (pinfunction "1_1") (pintype "passive"))
      (node (ref "R10") (pin "2") (pinfunction "2_2") (pintype "passive"))
      (node (ref "U$2") (pin "PE2") (pinfunction "PE2_PE2") (pintype "bidirectional"))
    )
    (net (code "85") (name "UART_RX") (class "Default")
      (node (ref "U$2") (pin "PB0") (pinfunction "PB0_PB0") (pintype "bidirectional"))
      (node (ref "U2") (pin "12") (pinfunction "R1OUT_12") (pintype "bidirectional"))
    )
    (net (code "86") (name "UART_TX") (class "Default")
      (node (ref "U$2") (pin "PB1") (pinfunction "PB1_PB1") (pintype "bidirectional"))
      (node (ref "U2") (pin "11") (pinfunction "T1IN_11") (pintype "bidirectional"))
    )
    (net (code "87") (name "VCC") (class "Default")
      (node (ref "C32") (pin "2") (pinfunction "2_2") (pintype "passive"))
      (node (ref "C33") (pin "2") (pinfunction "2_2") (pintype "passive"))
      (node (ref "C36") (pin "1") (pinfunction "+_1") (pintype "passive"))
      (node (ref "C46") (pin "1") (pinfunction "1_1") (pintype "passive"))
      (node (ref "D7") (pin "A") (pinfunction "A_A") (pintype "passive"))
      (node (ref "Q7") (pin "2") (pinfunction "S_2") (pintype "passive"))
      (node (ref "Q8") (pin "2") (pinfunction "S_2") (pintype "passive"))
      (node (ref "Q9") (pin "3") (pinfunction "D_3") (pintype "passive"))
      (node (ref "R3") (pin "2") (pinfunction "2_2") (pintype "passive"))
      (node (ref "R5") (pin "2") (pinfunction "2_2") (pintype "passive"))
      (node (ref "R6") (pin "2") (pinfunction "2_2") (pintype "passive"))
      (node (ref "R7") (pin "2") (pinfunction "2_2") (pintype "passive"))
      (node (ref "U$1") (pin "24") (pinfunction "REF_24") (pintype "bidirectional"))
      (node (ref "U$1") (pin "49") (pinfunction "VDD_SPI_49") (pintype "bidirectional"))
      (node (ref "U$10") (pin "P$1") (pinfunction "P$1_P$1") (pintype "bidirectional"))
      (node (ref "U$14") (pin "P$2") (pinfunction "P$2_P$2") (pintype "bidirectional"))
      (node (ref "U$2") (pin "+3V3") (pinfunction "+3V3_+3V3") (pintype "power_in"))
      (node (ref "U1") (pin "5") (pinfunction "VP_5") (pintype "bidirectional"))
      (node (ref "U2") (pin "16") (pinfunction "VCC_16") (pintype "bidirectional"))
    )
    (net (code "88") (name "unconnected-(J1-Pad2)") (class "Default")
      (node (ref "J1") (pin "2") (pinfunction "2_2") (pintype "bidirectional"))
    )
    (net (code "89") (name "unconnected-(U$1-EN_BUCK-Pad55)") (class "Default")
      (node (ref "U$1") (pin "55") (pinfunction "EN_BUCK_55") (pintype "bidirectional"))
    )
    (net (code "90") (name "unconnected-(U$2-PadPA5)") (class "Default")
      (node (ref "U$2") (pin "PA5") (pinfunction "PA5_PA5") (pintype "bidirectional"))
    )
    (net (code "91") (name "unconnected-(U$2-PadPB5)") (class "Default")
      (node (ref "U$2") (pin "PB5") (pinfunction "PB5_PB5") (pintype "bidirectional"))
    )
    (net (code "92") (name "unconnected-(U$2-PadPD7)") (class "Default")
      (node (ref "U$2") (pin "PD7") (pinfunction "PD7_PD7") (pintype "bidirectional"))
    )
    (net (code "93") (name "unconnected-(U$2-PadPE0)") (class "Default")
      (node (ref "U$2") (pin "PE0") (pinfunction "PE0_PE0") (pintype "bidirectional"))
    )
    (net (code "94") (name "unconnected-(U$2-PadPE3)") (class "Default")
      (node (ref "U$2") (pin "PE3") (pinfunction "PE3_PE3") (pintype "bidirectional"))
    )
    (net (code "95") (name "unconnected-(U$2-PadPE4)") (class "Default")
      (node (ref "U$2") (pin "PE4") (pinfunction "PE4_PE4") (pintype "bidirectional"))
    )
    (net (code "96") (name "unconnected-(U$2-PadPE5)") (class "Default")
      (node (ref "U$2") (pin "PE5") (pinfunction "PE5_PE5") (pintype "bidirectional"))
    )
    (net (code "97") (name "unconnected-(U$2-PadPF0)") (class "Default")
      (node (ref "U$2") (pin "PF0") (pinfunction "PF0_PF0") (pintype "bidirectional"))
    )
    (net (code "98") (name "unconnected-(U$2-PadPF1)") (class "Default")
      (node (ref "U$2") (pin "PF1") (pinfunction "PF1_PF1") (pintype "bidirectional"))
    )
    (net (code "99") (name "unconnected-(U$4-Pad2)") (class "Default")
      (node (ref "U$4") (pin "2") (pinfunction "2_2") (pintype "bidirectional"))
    )
    (net (code "100") (name "unconnected-(U2-R2IN-Pad8)") (class "Default")
      (node (ref "U2") (pin "8") (pinfunction "R2IN_8") (pintype "bidirectional"))
    )
    (net (code "101") (name "unconnected-(U2-R2OUT-Pad9)") (class "Default")
      (node (ref "U2") (pin "9") (pinfunction "R2OUT_9") (pintype "bidirectional"))
    )
    (net (code "102") (name "unconnected-(U2-T2IN-Pad10)") (class "Default")
      (node (ref "U2") (pin "10") (pinfunction "T2IN_10") (pintype "bidirectional"))
    )
    (net (code "103") (name "unconnected-(U2-T2OUT-Pad7)") (class "Default")
      (node (ref "U2") (pin "7") (pinfunction "T2OUT_7") (pintype "bidirectional"))
    )
  )
)
